# BaseBoard.net
KiCad netlist of a schematic drawn in EAGLE
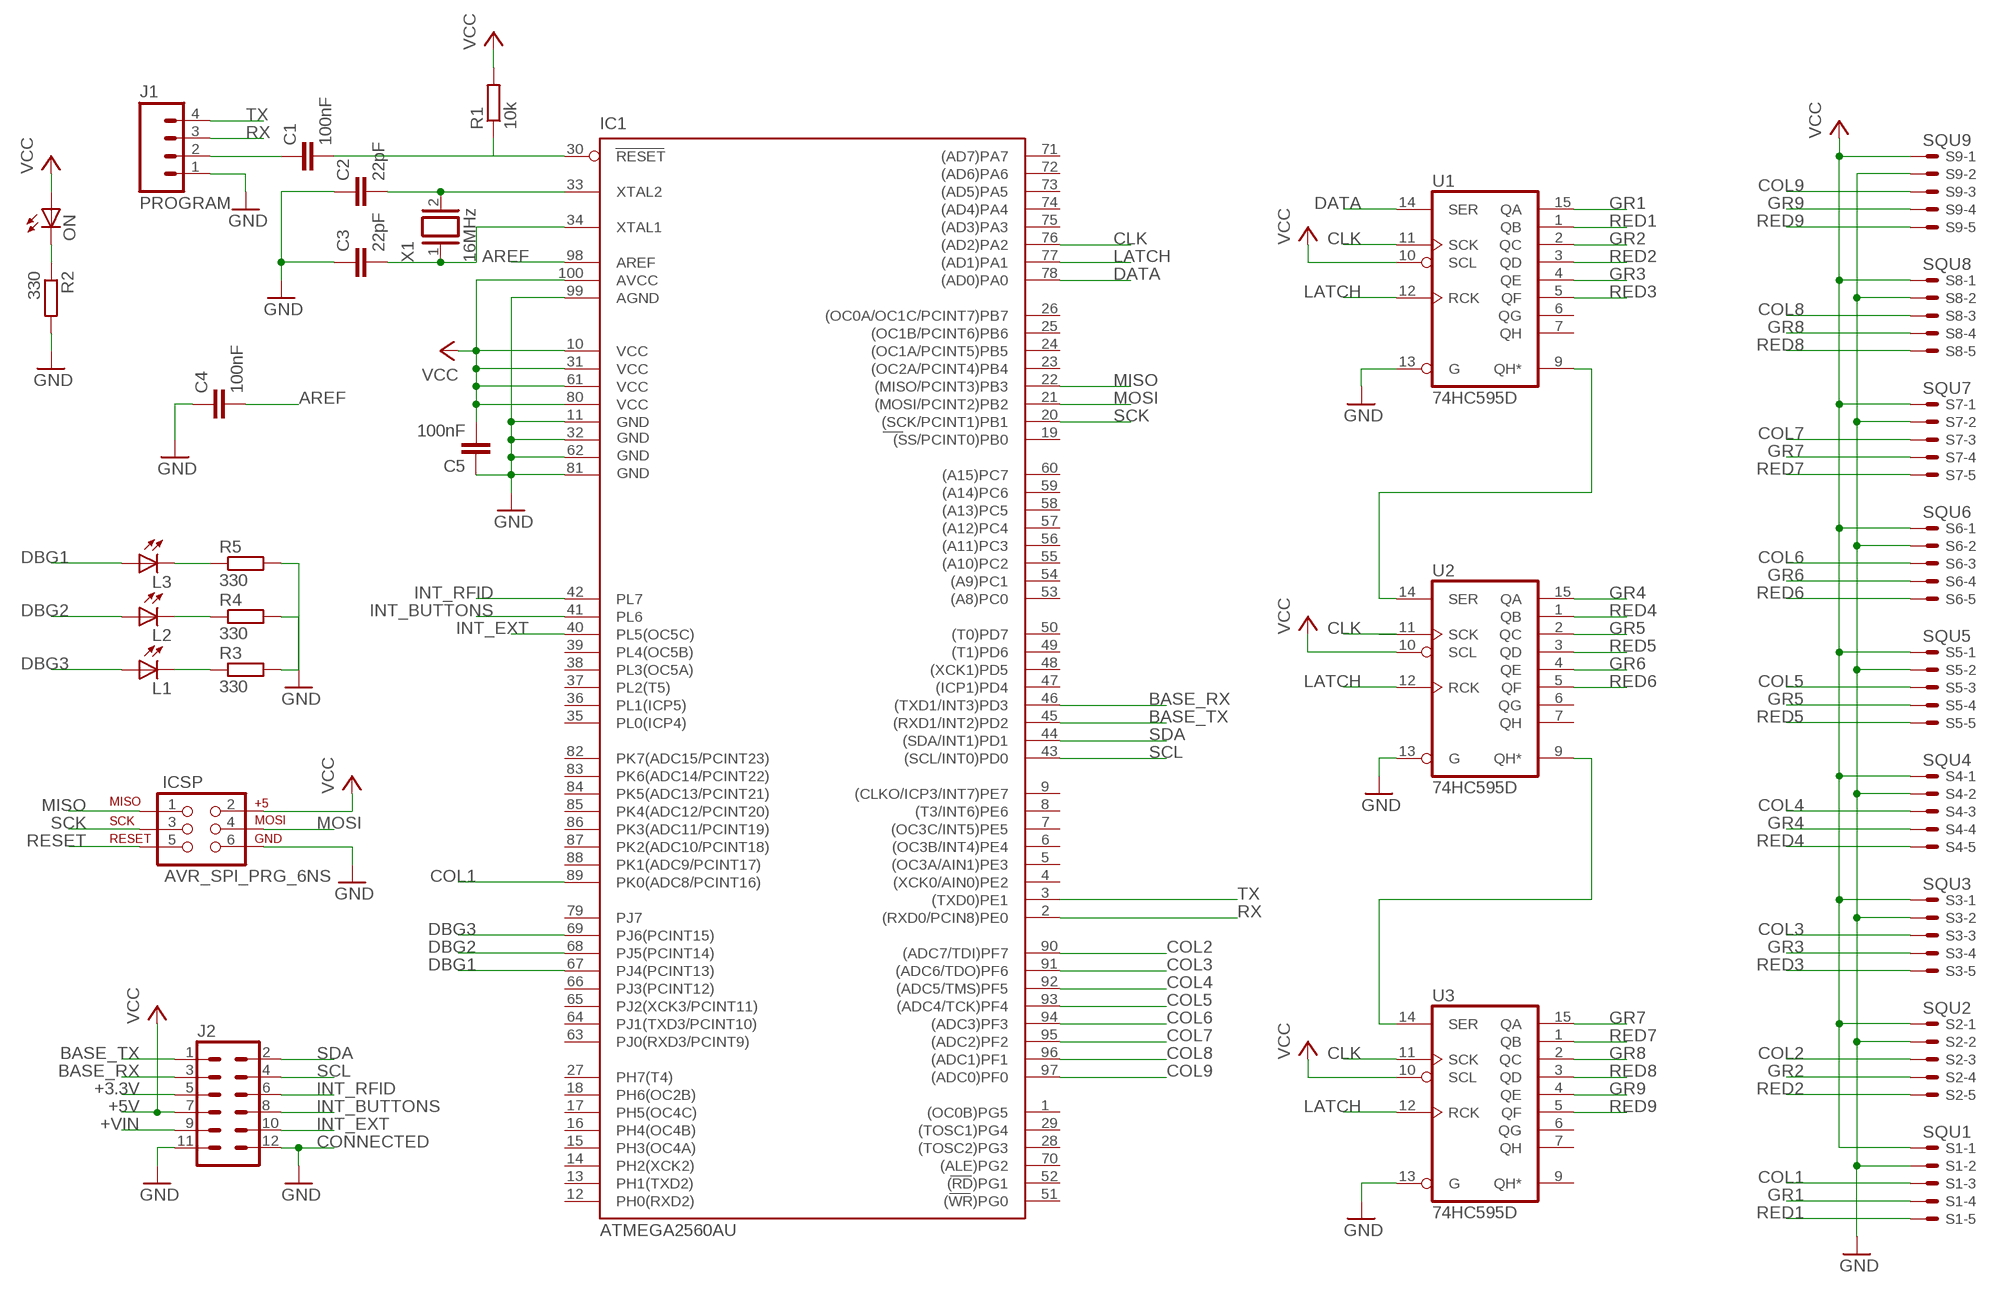
[diagram p0: schematic, sheet 1]

(export (version "E")
  (design (tool "Eeschema 10.0.6"))
  (components
    (comp (ref "C1")
      (value "100nF")
      (footprint "eagle-import:C0805")
      (libsource (lib "eagle-import") (part "C-EUC0805"))
    )
    (comp (ref "C2")
      (value "22pF")
      (footprint "eagle-import:C0805")
      (libsource (lib "eagle-import") (part "C-EUC0805"))
    )
    (comp (ref "C3")
      (value "22pF")
      (footprint "eagle-import:C0805")
      (libsource (lib "eagle-import") (part "C-EUC0805"))
    )
    (comp (ref "C4")
      (value "100nF")
      (footprint "eagle-import:C0805")
      (libsource (lib "eagle-import") (part "C-EUC0805"))
    )
    (comp (ref "C5")
      (value "100nF")
      (footprint "eagle-import:C0805")
      (libsource (lib "eagle-import") (part "C-EUC0805"))
    )
    (comp (ref "IC1")
      (value "ATMEGA2560AU")
      (footprint "eagle-import:TQFP100")
      (libsource (lib "eagle-import") (part "ATMEGA2560AU"))
    )
    (comp (ref "ICSP")
      (value "AVR_SPI_PRG_6NS")
      (footprint "eagle-import:2X3-NS")
      (libsource (lib "eagle-import") (part "AVR_SPI_PRG_6NS"))
    )
    (comp (ref "J1")
      (value "PROGRAM")
      (footprint "eagle-import:1X04")
      (libsource (lib "eagle-import") (part "M04PTH"))
    )
    (comp (ref "J2")
      (value "CON06X2-2MM")
      (footprint "eagle-import:CON06X2_2MM")
      (libsource (lib "eagle-import") (part "CON06X2-2MM"))
    )
    (comp (ref "L1")
      (value "LEDCHIP-LED0805")
      (footprint "eagle-import:CHIP-LED0805")
      (libsource (lib "eagle-import") (part "LEDCHIP-LED0805"))
    )
    (comp (ref "L2")
      (value "LEDCHIP-LED0805")
      (footprint "eagle-import:CHIP-LED0805")
      (libsource (lib "eagle-import") (part "LEDCHIP-LED0805"))
    )
    (comp (ref "L3")
      (value "LEDCHIP-LED0805")
      (footprint "eagle-import:CHIP-LED0805")
      (libsource (lib "eagle-import") (part "LEDCHIP-LED0805"))
    )
    (comp (ref "ON")
      (value "LEDCHIP-LED0805")
      (footprint "eagle-import:CHIP-LED0805")
      (libsource (lib "eagle-import") (part "LEDCHIP-LED0805"))
    )
    (comp (ref "R1")
      (value "10k")
      (footprint "eagle-import:R0805")
      (libsource (lib "eagle-import") (part "R-EU_R0805"))
    )
    (comp (ref "R2")
      (value "330")
      (footprint "eagle-import:R0805")
      (libsource (lib "eagle-import") (part "R-EU_R0805"))
    )
    (comp (ref "R3")
      (value "330")
      (footprint "eagle-import:R0805")
      (libsource (lib "eagle-import") (part "R-EU_R0805"))
    )
    (comp (ref "R4")
      (value "330")
      (footprint "eagle-import:R0805")
      (libsource (lib "eagle-import") (part "R-EU_R0805"))
    )
    (comp (ref "R5")
      (value "330")
      (footprint "eagle-import:R0805")
      (libsource (lib "eagle-import") (part "R-EU_R0805"))
    )
    (comp (ref "S1")
      (value "SQU1")
      (footprint "eagle-import:53261-05")
      (libsource (lib "eagle-import") (part "53?-05261"))
    )
    (comp (ref "S2")
      (value "SQU2")
      (footprint "eagle-import:53261-05")
      (libsource (lib "eagle-import") (part "53?-05261"))
    )
    (comp (ref "S3")
      (value "SQU3")
      (footprint "eagle-import:53261-05")
      (libsource (lib "eagle-import") (part "53?-05261"))
    )
    (comp (ref "S4")
      (value "SQU4")
      (footprint "eagle-import:53261-05")
      (libsource (lib "eagle-import") (part "53?-05261"))
    )
    (comp (ref "S5")
      (value "SQU5")
      (footprint "eagle-import:53261-05")
      (libsource (lib "eagle-import") (part "53?-05261"))
    )
    (comp (ref "S6")
      (value "SQU6")
      (footprint "eagle-import:53261-05")
      (libsource (lib "eagle-import") (part "53?-05261"))
    )
    (comp (ref "S7")
      (value "SQU7")
      (footprint "eagle-import:53261-05")
      (libsource (lib "eagle-import") (part "53?-05261"))
    )
    (comp (ref "S8")
      (value "SQU8")
      (footprint "eagle-import:53261-05")
      (libsource (lib "eagle-import") (part "53?-05261"))
    )
    (comp (ref "S9")
      (value "SQU9")
      (footprint "eagle-import:53261-05")
      (libsource (lib "eagle-import") (part "53?-05261"))
    )
    (comp (ref "U1")
      (value "74HC595D")
      (footprint "eagle-import:SO16")
      (libsource (lib "eagle-import") (part "74595DHC"))
    )
    (comp (ref "U2")
      (value "74HC595D")
      (footprint "eagle-import:SO16")
      (libsource (lib "eagle-import") (part "74595DHC"))
    )
    (comp (ref "U3")
      (value "74HC595D")
      (footprint "eagle-import:SO16")
      (libsource (lib "eagle-import") (part "74595DHC"))
    )
    (comp (ref "X1")
      (value "16MHz")
      (footprint "eagle-import:QS")
      (libsource (lib "eagle-import") (part "XTAL/S"))
    )
  )
  (nets
    (net (code "1") (name "/+3.3V") (class "Default")
      (node (ref "J2") (pin "5") (pinfunction "5_5") (pintype "passive"))
    )
    (net (code "2") (name "/+VIN") (class "Default")
      (node (ref "J2") (pin "9") (pinfunction "9_9") (pintype "passive"))
    )
    (net (code "3") (name "/AREF") (class "Default")
      (node (ref "C4") (pin "2") (pinfunction "2_2") (pintype "passive"))
      (node (ref "IC1") (pin "98") (pinfunction "AREF_98") (pintype "bidirectional"))
    )
    (net (code "4") (name "/BASE_RX") (class "Default")
      (node (ref "IC1") (pin "46") (pinfunction "(TXD1/INT3)PD3_46") (pintype "bidirectional"))
      (node (ref "J2") (pin "3") (pinfunction "3_3") (pintype "passive"))
    )
    (net (code "5") (name "/BASE_TX") (class "Default")
      (node (ref "IC1") (pin "45") (pinfunction "(RXD1/INT2)PD2_45") (pintype "bidirectional"))
      (node (ref "J2") (pin "1") (pinfunction "1_1") (pintype "passive"))
    )
    (net (code "6") (name "/CLK") (class "Default")
      (node (ref "IC1") (pin "76") (pinfunction "(AD2)PA2_76") (pintype "bidirectional"))
      (node (ref "U1") (pin "11") (pinfunction "SCK_11") (pintype "input"))
      (node (ref "U2") (pin "11") (pinfunction "SCK_11") (pintype "input"))
      (node (ref "U3") (pin "11") (pinfunction "SCK_11") (pintype "input"))
    )
    (net (code "7") (name "/COL1") (class "Default")
      (node (ref "IC1") (pin "89") (pinfunction "PK0(ADC8/PCINT16)_89") (pintype "bidirectional"))
      (node (ref "S1") (pin "3") (pinfunction "S_3") (pintype "passive"))
    )
    (net (code "8") (name "/COL2") (class "Default")
      (node (ref "IC1") (pin "90") (pinfunction "(ADC7/TDI)PF7_90") (pintype "bidirectional"))
      (node (ref "S2") (pin "3") (pinfunction "S_3") (pintype "passive"))
    )
    (net (code "9") (name "/COL3") (class "Default")
      (node (ref "IC1") (pin "91") (pinfunction "(ADC6/TDO)PF6_91") (pintype "bidirectional"))
      (node (ref "S3") (pin "3") (pinfunction "S_3") (pintype "passive"))
    )
    (net (code "10") (name "/COL4") (class "Default")
      (node (ref "IC1") (pin "92") (pinfunction "(ADC5/TMS)PF5_92") (pintype "bidirectional"))
      (node (ref "S4") (pin "3") (pinfunction "S_3") (pintype "passive"))
    )
    (net (code "11") (name "/COL5") (class "Default")
      (node (ref "IC1") (pin "93") (pinfunction "(ADC4/TCK)PF4_93") (pintype "bidirectional"))
      (node (ref "S5") (pin "3") (pinfunction "S_3") (pintype "passive"))
    )
    (net (code "12") (name "/COL6") (class "Default")
      (node (ref "IC1") (pin "94") (pinfunction "(ADC3)PF3_94") (pintype "bidirectional"))
      (node (ref "S6") (pin "3") (pinfunction "S_3") (pintype "passive"))
    )
    (net (code "13") (name "/COL7") (class "Default")
      (node (ref "IC1") (pin "95") (pinfunction "(ADC2)PF2_95") (pintype "bidirectional"))
      (node (ref "S7") (pin "3") (pinfunction "S_3") (pintype "passive"))
    )
    (net (code "14") (name "/COL8") (class "Default")
      (node (ref "IC1") (pin "96") (pinfunction "(ADC1)PF1_96") (pintype "bidirectional"))
      (node (ref "S8") (pin "3") (pinfunction "S_3") (pintype "passive"))
    )
    (net (code "15") (name "/COL9") (class "Default")
      (node (ref "IC1") (pin "97") (pinfunction "(ADC0)PF0_97") (pintype "bidirectional"))
      (node (ref "S9") (pin "3") (pinfunction "S_3") (pintype "passive"))
    )
    (net (code "16") (name "/DATA") (class "Default")
      (node (ref "IC1") (pin "78") (pinfunction "(AD0)PA0_78") (pintype "bidirectional"))
      (node (ref "U1") (pin "14") (pinfunction "SER_14") (pintype "input"))
    )
    (net (code "17") (name "/DBG1") (class "Default")
      (node (ref "IC1") (pin "67") (pinfunction "PJ4(PCINT13)_67") (pintype "bidirectional"))
      (node (ref "L3") (pin "A") (pinfunction "A_A") (pintype "passive"))
    )
    (net (code "18") (name "/DBG2") (class "Default")
      (node (ref "IC1") (pin "68") (pinfunction "PJ5(PCINT14)_68") (pintype "bidirectional"))
      (node (ref "L2") (pin "A") (pinfunction "A_A") (pintype "passive"))
    )
    (net (code "19") (name "/DBG3") (class "Default")
      (node (ref "IC1") (pin "69") (pinfunction "PJ6(PCINT15)_69") (pintype "bidirectional"))
      (node (ref "L1") (pin "A") (pinfunction "A_A") (pintype "passive"))
    )
    (net (code "20") (name "/GR1") (class "Default")
      (node (ref "S1") (pin "4") (pinfunction "S_4") (pintype "passive"))
      (node (ref "U1") (pin "15") (pinfunction "QA_15") (pintype "tri_state"))
    )
    (net (code "21") (name "/GR2") (class "Default")
      (node (ref "S2") (pin "4") (pinfunction "S_4") (pintype "passive"))
      (node (ref "U1") (pin "2") (pinfunction "QC_2") (pintype "tri_state"))
    )
    (net (code "22") (name "/GR3") (class "Default")
      (node (ref "S3") (pin "4") (pinfunction "S_4") (pintype "passive"))
      (node (ref "U1") (pin "4") (pinfunction "QE_4") (pintype "tri_state"))
    )
    (net (code "23") (name "/GR4") (class "Default")
      (node (ref "S4") (pin "4") (pinfunction "S_4") (pintype "passive"))
      (node (ref "U2") (pin "15") (pinfunction "QA_15") (pintype "tri_state"))
    )
    (net (code "24") (name "/GR5") (class "Default")
      (node (ref "S5") (pin "4") (pinfunction "S_4") (pintype "passive"))
      (node (ref "U2") (pin "2") (pinfunction "QC_2") (pintype "tri_state"))
    )
    (net (code "25") (name "/GR6") (class "Default")
      (node (ref "S6") (pin "4") (pinfunction "S_4") (pintype "passive"))
      (node (ref "U2") (pin "4") (pinfunction "QE_4") (pintype "tri_state"))
    )
    (net (code "26") (name "/GR7") (class "Default")
      (node (ref "S7") (pin "4") (pinfunction "S_4") (pintype "passive"))
      (node (ref "U3") (pin "15") (pinfunction "QA_15") (pintype "tri_state"))
    )
    (net (code "27") (name "/GR8") (class "Default")
      (node (ref "S8") (pin "4") (pinfunction "S_4") (pintype "passive"))
      (node (ref "U3") (pin "2") (pinfunction "QC_2") (pintype "tri_state"))
    )
    (net (code "28") (name "/GR9") (class "Default")
      (node (ref "S9") (pin "4") (pinfunction "S_4") (pintype "passive"))
      (node (ref "U3") (pin "4") (pinfunction "QE_4") (pintype "tri_state"))
    )
    (net (code "29") (name "/INT_BUTTONS") (class "Default")
      (node (ref "IC1") (pin "41") (pinfunction "PL6_41") (pintype "bidirectional"))
      (node (ref "J2") (pin "8") (pinfunction "8_8") (pintype "passive"))
    )
    (net (code "30") (name "/INT_EXT") (class "Default")
      (node (ref "IC1") (pin "40") (pinfunction "PL5(OC5C)_40") (pintype "bidirectional"))
      (node (ref "J2") (pin "10") (pinfunction "10_10") (pintype "passive"))
    )
    (net (code "31") (name "/INT_RFID") (class "Default")
      (node (ref "IC1") (pin "42") (pinfunction "PL7_42") (pintype "bidirectional"))
      (node (ref "J2") (pin "6") (pinfunction "6_6") (pintype "passive"))
    )
    (net (code "32") (name "/LATCH") (class "Default")
      (node (ref "IC1") (pin "77") (pinfunction "(AD1)PA1_77") (pintype "bidirectional"))
      (node (ref "U1") (pin "12") (pinfunction "RCK_12") (pintype "input"))
      (node (ref "U2") (pin "12") (pinfunction "RCK_12") (pintype "input"))
      (node (ref "U3") (pin "12") (pinfunction "RCK_12") (pintype "input"))
    )
    (net (code "33") (name "/MISO") (class "Default")
      (node (ref "IC1") (pin "22") (pinfunction "(MISO/PCINT3)PB3_22") (pintype "bidirectional"))
      (node (ref "ICSP") (pin "1") (pinfunction "1_1") (pintype "passive"))
    )
    (net (code "34") (name "/MOSI") (class "Default")
      (node (ref "IC1") (pin "21") (pinfunction "(MOSI/PCINT2)PB2_21") (pintype "bidirectional"))
      (node (ref "ICSP") (pin "4") (pinfunction "4_4") (pintype "passive"))
    )
    (net (code "35") (name "/RED1") (class "Default")
      (node (ref "S1") (pin "5") (pinfunction "S_5") (pintype "passive"))
      (node (ref "U1") (pin "1") (pinfunction "QB_1") (pintype "tri_state"))
    )
    (net (code "36") (name "/RED2") (class "Default")
      (node (ref "S2") (pin "5") (pinfunction "S_5") (pintype "passive"))
      (node (ref "U1") (pin "3") (pinfunction "QD_3") (pintype "tri_state"))
    )
    (net (code "37") (name "/RED3") (class "Default")
      (node (ref "S3") (pin "5") (pinfunction "S_5") (pintype "passive"))
      (node (ref "U1") (pin "5") (pinfunction "QF_5") (pintype "tri_state"))
    )
    (net (code "38") (name "/RED4") (class "Default")
      (node (ref "S4") (pin "5") (pinfunction "S_5") (pintype "passive"))
      (node (ref "U2") (pin "1") (pinfunction "QB_1") (pintype "tri_state"))
    )
    (net (code "39") (name "/RED5") (class "Default")
      (node (ref "S5") (pin "5") (pinfunction "S_5") (pintype "passive"))
      (node (ref "U2") (pin "3") (pinfunction "QD_3") (pintype "tri_state"))
    )
    (net (code "40") (name "/RED6") (class "Default")
      (node (ref "S6") (pin "5") (pinfunction "S_5") (pintype "passive"))
      (node (ref "U2") (pin "5") (pinfunction "QF_5") (pintype "tri_state"))
    )
    (net (code "41") (name "/RED7") (class "Default")
      (node (ref "S7") (pin "5") (pinfunction "S_5") (pintype "passive"))
      (node (ref "U3") (pin "1") (pinfunction "QB_1") (pintype "tri_state"))
    )
    (net (code "42") (name "/RED8") (class "Default")
      (node (ref "S8") (pin "5") (pinfunction "S_5") (pintype "passive"))
      (node (ref "U3") (pin "3") (pinfunction "QD_3") (pintype "tri_state"))
    )
    (net (code "43") (name "/RED9") (class "Default")
      (node (ref "S9") (pin "5") (pinfunction "S_5") (pintype "passive"))
      (node (ref "U3") (pin "5") (pinfunction "QF_5") (pintype "tri_state"))
    )
    (net (code "44") (name "/RESET") (class "Default")
      (node (ref "C1") (pin "2") (pinfunction "2_2") (pintype "passive"))
      (node (ref "IC1") (pin "30") (pinfunction "RESET_30") (pintype "input"))
      (node (ref "ICSP") (pin "5") (pinfunction "5_5") (pintype "passive"))
      (node (ref "R1") (pin "1") (pinfunction "1_1") (pintype "passive"))
    )
    (net (code "45") (name "/RX") (class "Default")
      (node (ref "IC1") (pin "2") (pinfunction "(RXD0/PCIN8)PE0_2") (pintype "bidirectional"))
      (node (ref "J1") (pin "3") (pinfunction "3_3") (pintype "passive"))
    )
    (net (code "46") (name "/SCK") (class "Default")
      (node (ref "IC1") (pin "20") (pinfunction "(SCK/PCINT1)PB1_20") (pintype "bidirectional"))
      (node (ref "ICSP") (pin "3") (pinfunction "3_3") (pintype "passive"))
    )
    (net (code "47") (name "/SCL") (class "Default")
      (node (ref "IC1") (pin "43") (pinfunction "(SCL/INT0)PD0_43") (pintype "bidirectional"))
      (node (ref "J2") (pin "4") (pinfunction "4_4") (pintype "passive"))
    )
    (net (code "48") (name "/SDA") (class "Default")
      (node (ref "IC1") (pin "44") (pinfunction "(SDA/INT1)PD1_44") (pintype "bidirectional"))
      (node (ref "J2") (pin "2") (pinfunction "2_2") (pintype "passive"))
    )
    (net (code "49") (name "/TX") (class "Default")
      (node (ref "IC1") (pin "3") (pinfunction "(TXD0)PE1_3") (pintype "bidirectional"))
      (node (ref "J1") (pin "4") (pinfunction "4_4") (pintype "passive"))
    )
    (net (code "50") (name "GND") (class "Default")
      (node (ref "C2") (pin "1") (pinfunction "1_1") (pintype "passive"))
      (node (ref "C3") (pin "1") (pinfunction "1_1") (pintype "passive"))
      (node (ref "C4") (pin "1") (pinfunction "1_1") (pintype "passive"))
      (node (ref "C5") (pin "1") (pinfunction "1_1") (pintype "passive"))
      (node (ref "IC1") (pin "11") (pinfunction "GND_11") (pintype "power_in"))
      (node (ref "IC1") (pin "32") (pinfunction "GND1_32") (pintype "power_in"))
      (node (ref "IC1") (pin "62") (pinfunction "GND2_62") (pintype "power_in"))
      (node (ref "IC1") (pin "81") (pinfunction "GND3_81") (pintype "power_in"))
      (node (ref "IC1") (pin "99") (pinfunction "AGND_99") (pintype "power_in"))
      (node (ref "ICSP") (pin "6") (pinfunction "6_6") (pintype "passive"))
      (node (ref "J1") (pin "1") (pinfunction "1_1") (pintype "passive"))
      (node (ref "J2") (pin "11") (pinfunction "11_11") (pintype "passive"))
      (node (ref "J2") (pin "12") (pinfunction "12_12") (pintype "passive"))
      (node (ref "R2") (pin "2") (pinfunction "2_2") (pintype "passive"))
      (node (ref "R3") (pin "2") (pinfunction "2_2") (pintype "passive"))
      (node (ref "R4") (pin "2") (pinfunction "2_2") (pintype "passive"))
      (node (ref "R5") (pin "2") (pinfunction "2_2") (pintype "passive"))
      (node (ref "S1") (pin "2") (pinfunction "S_2") (pintype "passive"))
      (node (ref "S2") (pin "2") (pinfunction "S_2") (pintype "passive"))
      (node (ref "S3") (pin "2") (pinfunction "S_2") (pintype "passive"))
      (node (ref "S4") (pin "2") (pinfunction "S_2") (pintype "passive"))
      (node (ref "S5") (pin "2") (pinfunction "S_2") (pintype "passive"))
      (node (ref "S6") (pin "2") (pinfunction "S_2") (pintype "passive"))
      (node (ref "S7") (pin "2") (pinfunction "S_2") (pintype "passive"))
      (node (ref "S8") (pin "2") (pinfunction "S_2") (pintype "passive"))
      (node (ref "S9") (pin "2") (pinfunction "S_2") (pintype "passive"))
      (node (ref "U1") (pin "13") (pinfunction "G_13") (pintype "input"))
      (node (ref "U2") (pin "13") (pinfunction "G_13") (pintype "input"))
      (node (ref "U3") (pin "13") (pinfunction "G_13") (pintype "input"))
    )
    (net (code "51") (name "Net-(C1-Pad1)") (class "Default")
      (node (ref "C1") (pin "1") (pinfunction "1_1") (pintype "passive"))
      (node (ref "J1") (pin "2") (pinfunction "2_2") (pintype "passive"))
    )
    (net (code "52") (name "Net-(IC1-XTAL1)") (class "Default")
      (node (ref "C3") (pin "2") (pinfunction "2_2") (pintype "passive"))
      (node (ref "IC1") (pin "34") (pinfunction "XTAL1_34") (pintype "input"))
      (node (ref "X1") (pin "1") (pinfunction "1_1") (pintype "passive"))
    )
    (net (code "53") (name "Net-(IC1-XTAL2)") (class "Default")
      (node (ref "C2") (pin "2") (pinfunction "2_2") (pintype "passive"))
      (node (ref "IC1") (pin "33") (pinfunction "XTAL2_33") (pintype "output"))
      (node (ref "X1") (pin "2") (pinfunction "2_2") (pintype "passive"))
    )
    (net (code "54") (name "Net-(L1-PadC)") (class "Default")
      (node (ref "L1") (pin "C") (pinfunction "C_C") (pintype "passive"))
      (node (ref "R3") (pin "1") (pinfunction "1_1") (pintype "passive"))
    )
    (net (code "55") (name "Net-(L2-PadC)") (class "Default")
      (node (ref "L2") (pin "C") (pinfunction "C_C") (pintype "passive"))
      (node (ref "R4") (pin "1") (pinfunction "1_1") (pintype "passive"))
    )
    (net (code "56") (name "Net-(L3-PadC)") (class "Default")
      (node (ref "L3") (pin "C") (pinfunction "C_C") (pintype "passive"))
      (node (ref "R5") (pin "1") (pinfunction "1_1") (pintype "passive"))
    )
    (net (code "57") (name "Net-(ON-PadC)") (class "Default")
      (node (ref "ON") (pin "C") (pinfunction "C_C") (pintype "passive"))
      (node (ref "R2") (pin "1") (pinfunction "1_1") (pintype "passive"))
    )
    (net (code "58") (name "Net-(U1A-QH*)") (class "Default")
      (node (ref "U1") (pin "9") (pinfunction "QH*_9") (pintype "tri_state"))
      (node (ref "U2") (pin "14") (pinfunction "SER_14") (pintype "input"))
    )
    (net (code "59") (name "Net-(U2A-QH*)") (class "Default")
      (node (ref "U2") (pin "9") (pinfunction "QH*_9") (pintype "tri_state"))
      (node (ref "U3") (pin "14") (pinfunction "SER_14") (pintype "input"))
    )
    (net (code "60") (name "VCC") (class "Default")
      (node (ref "C5") (pin "2") (pinfunction "2_2") (pintype "passive"))
      (node (ref "IC1") (pin "10") (pinfunction "VCC_10") (pintype "power_in"))
      (node (ref "IC1") (pin "100") (pinfunction "AVCC_100") (pintype "power_in"))
      (node (ref "IC1") (pin "31") (pinfunction "VCC1_31") (pintype "power_in"))
      (node (ref "IC1") (pin "61") (pinfunction "VCC2_61") (pintype "power_in"))
      (node (ref "IC1") (pin "80") (pinfunction "VCC3_80") (pintype "power_in"))
      (node (ref "ICSP") (pin "2") (pinfunction "2_2") (pintype "passive"))
      (node (ref "J2") (pin "7") (pinfunction "7_7") (pintype "passive"))
      (node (ref "ON") (pin "A") (pinfunction "A_A") (pintype "passive"))
      (node (ref "R1") (pin "2") (pinfunction "2_2") (pintype "passive"))
      (node (ref "S1") (pin "1") (pinfunction "S_1") (pintype "passive"))
      (node (ref "S2") (pin "1") (pinfunction "S_1") (pintype "passive"))
      (node (ref "S3") (pin "1") (pinfunction "S_1") (pintype "passive"))
      (node (ref "S4") (pin "1") (pinfunction "S_1") (pintype "passive"))
      (node (ref "S5") (pin "1") (pinfunction "S_1") (pintype "passive"))
      (node (ref "S6") (pin "1") (pinfunction "S_1") (pintype "passive"))
      (node (ref "S7") (pin "1") (pinfunction "S_1") (pintype "passive"))
      (node (ref "S8") (pin "1") (pinfunction "S_1") (pintype "passive"))
      (node (ref "S9") (pin "1") (pinfunction "S_1") (pintype "passive"))
      (node (ref "U1") (pin "10") (pinfunction "SCL_10") (pintype "input"))
      (node (ref "U2") (pin "10") (pinfunction "SCL_10") (pintype "input"))
      (node (ref "U3") (pin "10") (pinfunction "SCL_10") (pintype "input"))
    )
    (net (code "61") (name "unconnected-(IC1-(A8)PC0-Pad53)") (class "Default")
      (node (ref "IC1") (pin "53") (pinfunction "(A8)PC0_53") (pintype "bidirectional"))
    )
    (net (code "62") (name "unconnected-(IC1-(A9)PC1-Pad54)") (class "Default")
      (node (ref "IC1") (pin "54") (pinfunction "(A9)PC1_54") (pintype "bidirectional"))
    )
    (net (code "63") (name "unconnected-(IC1-(A10)PC2-Pad55)") (class "Default")
      (node (ref "IC1") (pin "55") (pinfunction "(A10)PC2_55") (pintype "bidirectional"))
    )
    (net (code "64") (name "unconnected-(IC1-(A11)PC3-Pad56)") (class "Default")
      (node (ref "IC1") (pin "56") (pinfunction "(A11)PC3_56") (pintype "bidirectional"))
    )
    (net (code "65") (name "unconnected-(IC1-(A12)PC4-Pad57)") (class "Default")
      (node (ref "IC1") (pin "57") (pinfunction "(A12)PC4_57") (pintype "bidirectional"))
    )
    (net (code "66") (name "unconnected-(IC1-(A13)PC5-Pad58)") (class "Default")
      (node (ref "IC1") (pin "58") (pinfunction "(A13)PC5_58") (pintype "bidirectional"))
    )
    (net (code "67") (name "unconnected-(IC1-(A14)PC6-Pad59)") (class "Default")
      (node (ref "IC1") (pin "59") (pinfunction "(A14)PC6_59") (pintype "bidirectional"))
    )
    (net (code "68") (name "unconnected-(IC1-(A15)PC7-Pad60)") (class "Default")
      (node (ref "IC1") (pin "60") (pinfunction "(A15)PC7_60") (pintype "bidirectional"))
    )
    (net (code "69") (name "unconnected-(IC1-(AD3)PA3-Pad75)") (class "Default")
      (node (ref "IC1") (pin "75") (pinfunction "(AD3)PA3_75") (pintype "bidirectional"))
    )
    (net (code "70") (name "unconnected-(IC1-(AD4)PA4-Pad74)") (class "Default")
      (node (ref "IC1") (pin "74") (pinfunction "(AD4)PA4_74") (pintype "bidirectional"))
    )
    (net (code "71") (name "unconnected-(IC1-(AD5)PA5-Pad73)") (class "Default")
      (node (ref "IC1") (pin "73") (pinfunction "(AD5)PA5_73") (pintype "bidirectional"))
    )
    (net (code "72") (name "unconnected-(IC1-(AD6)PA6-Pad72)") (class "Default")
      (node (ref "IC1") (pin "72") (pinfunction "(AD6)PA6_72") (pintype "bidirectional"))
    )
    (net (code "73") (name "unconnected-(IC1-(AD7)PA7-Pad71)") (class "Default")
      (node (ref "IC1") (pin "71") (pinfunction "(AD7)PA7_71") (pintype "bidirectional"))
    )
    (net (code "74") (name "unconnected-(IC1-(ALE)PG2-Pad70)") (class "Default")
      (node (ref "IC1") (pin "70") (pinfunction "(ALE)PG2_70") (pintype "bidirectional"))
    )
    (net (code "75") (name "unconnected-(IC1-(CLKO{slash}ICP3{slash}INT7)PE7-Pad9)") (class "Default")
      (node (ref "IC1") (pin "9") (pinfunction "(CLKO/ICP3/INT7)PE7_9") (pintype "bidirectional"))
    )
    (net (code "76") (name "unconnected-(IC1-(ICP1)PD4-Pad47)") (class "Default")
      (node (ref "IC1") (pin "47") (pinfunction "(ICP1)PD4_47") (pintype "bidirectional"))
    )
    (net (code "77") (name "unconnected-(IC1-(OC0A{slash}OC1C{slash}PCINT7)PB7-Pad26)") (class "Default")
      (node (ref "IC1") (pin "26") (pinfunction "(OC0A/OC1C/PCINT7)PB7_26") (pintype "bidirectional"))
    )
    (net (code "78") (name "unconnected-(IC1-(OC0B)PG5-Pad1)") (class "Default")
      (node (ref "IC1") (pin "1") (pinfunction "(OC0B)PG5_1") (pintype "bidirectional"))
    )
    (net (code "79") (name "unconnected-(IC1-(OC1A{slash}PCINT5)PB5-Pad24)") (class "Default")
      (node (ref "IC1") (pin "24") (pinfunction "(OC1A/PCINT5)PB5_24") (pintype "bidirectional"))
    )
    (net (code "80") (name "unconnected-(IC1-(OC1B{slash}PCINT6)PB6-Pad25)") (class "Default")
      (node (ref "IC1") (pin "25") (pinfunction "(OC1B/PCINT6)PB6_25") (pintype "bidirectional"))
    )
    (net (code "81") (name "unconnected-(IC1-(OC2A{slash}PCINT4)PB4-Pad23)") (class "Default")
      (node (ref "IC1") (pin "23") (pinfunction "(OC2A/PCINT4)PB4_23") (pintype "bidirectional"))
    )
    (net (code "82") (name "unconnected-(IC1-(OC3A{slash}AIN1)PE3-Pad5)") (class "Default")
      (node (ref "IC1") (pin "5") (pinfunction "(OC3A/AIN1)PE3_5") (pintype "bidirectional"))
    )
    (net (code "83") (name "unconnected-(IC1-(OC3B{slash}INT4)PE4-Pad6)") (class "Default")
      (node (ref "IC1") (pin "6") (pinfunction "(OC3B/INT4)PE4_6") (pintype "bidirectional"))
    )
    (net (code "84") (name "unconnected-(IC1-(OC3C{slash}INT5)PE5-Pad7)") (class "Default")
      (node (ref "IC1") (pin "7") (pinfunction "(OC3C/INT5)PE5_7") (pintype "bidirectional"))
    )
    (net (code "85") (name "unconnected-(IC1-(RD)PG1-Pad52)") (class "Default")
      (node (ref "IC1") (pin "52") (pinfunction "(RD)PG1_52") (pintype "bidirectional"))
    )
    (net (code "86") (name "unconnected-(IC1-(SS{slash}PCINT0)PB0-Pad19)") (class "Default")
      (node (ref "IC1") (pin "19") (pinfunction "(SS/PCINT0)PB0_19") (pintype "bidirectional"))
    )
    (net (code "87") (name "unconnected-(IC1-(T0)PD7-Pad50)") (class "Default")
      (node (ref "IC1") (pin "50") (pinfunction "(T0)PD7_50") (pintype "bidirectional"))
    )
    (net (code "88") (name "unconnected-(IC1-(T1)PD6-Pad49)") (class "Default")
      (node (ref "IC1") (pin "49") (pinfunction "(T1)PD6_49") (pintype "bidirectional"))
    )
    (net (code "89") (name "unconnected-(IC1-(T3{slash}INT6)PE6-Pad8)") (class "Default")
      (node (ref "IC1") (pin "8") (pinfunction "(T3/INT6)PE6_8") (pintype "bidirectional"))
    )
    (net (code "90") (name "unconnected-(IC1-(TOSC1)PG4-Pad29)") (class "Default")
      (node (ref "IC1") (pin "29") (pinfunction "(TOSC1)PG4_29") (pintype "bidirectional"))
    )
    (net (code "91") (name "unconnected-(IC1-(TOSC2)PG3-Pad28)") (class "Default")
      (node (ref "IC1") (pin "28") (pinfunction "(TOSC2)PG3_28") (pintype "bidirectional"))
    )
    (net (code "92") (name "unconnected-(IC1-(WR)PG0-Pad51)") (class "Default")
      (node (ref "IC1") (pin "51") (pinfunction "(WR)PG0_51") (pintype "bidirectional"))
    )
    (net (code "93") (name "unconnected-(IC1-(XCK0{slash}AIN0)PE2-Pad4)") (class "Default")
      (node (ref "IC1") (pin "4") (pinfunction "(XCK0/AIN0)PE2_4") (pintype "bidirectional"))
    )
    (net (code "94") (name "unconnected-(IC1-(XCK1)PD5-Pad48)") (class "Default")
      (node (ref "IC1") (pin "48") (pinfunction "(XCK1)PD5_48") (pintype "bidirectional"))
    )
    (net (code "95") (name "unconnected-(IC1-PH0(RXD2)-Pad12)") (class "Default")
      (node (ref "IC1") (pin "12") (pinfunction "PH0(RXD2)_12") (pintype "bidirectional"))
    )
    (net (code "96") (name "unconnected-(IC1-PH1(TXD2)-Pad13)") (class "Default")
      (node (ref "IC1") (pin "13") (pinfunction "PH1(TXD2)_13") (pintype "bidirectional"))
    )
    (net (code "97") (name "unconnected-(IC1-PH2(XCK2)-Pad14)") (class "Default")
      (node (ref "IC1") (pin "14") (pinfunction "PH2(XCK2)_14") (pintype "bidirectional"))
    )
    (net (code "98") (name "unconnected-(IC1-PH3(OC4A)-Pad15)") (class "Default")
      (node (ref "IC1") (pin "15") (pinfunction "PH3(OC4A)_15") (pintype "bidirectional"))
    )
    (net (code "99") (name "unconnected-(IC1-PH4(OC4B)-Pad16)") (class "Default")
      (node (ref "IC1") (pin "16") (pinfunction "PH4(OC4B)_16") (pintype "bidirectional"))
    )
    (net (code "100") (name "unconnected-(IC1-PH5(OC4C)-Pad17)") (class "Default")
      (node (ref "IC1") (pin "17") (pinfunction "PH5(OC4C)_17") (pintype "bidirectional"))
    )
    (net (code "101") (name "unconnected-(IC1-PH6(OC2B)-Pad18)") (class "Default")
      (node (ref "IC1") (pin "18") (pinfunction "PH6(OC2B)_18") (pintype "bidirectional"))
    )
    (net (code "102") (name "unconnected-(IC1-PH7(T4)-Pad27)") (class "Default")
      (node (ref "IC1") (pin "27") (pinfunction "PH7(T4)_27") (pintype "bidirectional"))
    )
    (net (code "103") (name "unconnected-(IC1-PJ0(RXD3{slash}PCINT9)-Pad63)") (class "Default")
      (node (ref "IC1") (pin "63") (pinfunction "PJ0(RXD3/PCINT9)_63") (pintype "bidirectional"))
    )
    (net (code "104") (name "unconnected-(IC1-PJ1(TXD3{slash}PCINT10)-Pad64)") (class "Default")
      (node (ref "IC1") (pin "64") (pinfunction "PJ1(TXD3/PCINT10)_64") (pintype "bidirectional"))
    )
    (net (code "105") (name "unconnected-(IC1-PJ2(XCK3{slash}PCINT11)-Pad65)") (class "Default")
      (node (ref "IC1") (pin "65") (pinfunction "PJ2(XCK3/PCINT11)_65") (pintype "bidirectional"))
    )
    (net (code "106") (name "unconnected-(IC1-PJ3(PCINT12)-Pad66)") (class "Default")
      (node (ref "IC1") (pin "66") (pinfunction "PJ3(PCINT12)_66") (pintype "bidirectional"))
    )
    (net (code "107") (name "unconnected-(IC1-PJ7-Pad79)") (class "Default")
      (node (ref "IC1") (pin "79") (pinfunction "PJ7_79") (pintype "bidirectional"))
    )
    (net (code "108") (name "unconnected-(IC1-PK1(ADC9{slash}PCINT17)-Pad88)") (class "Default")
      (node (ref "IC1") (pin "88") (pinfunction "PK1(ADC9/PCINT17)_88") (pintype "bidirectional"))
    )
    (net (code "109") (name "unconnected-(IC1-PK2(ADC10{slash}PCINT18)-Pad87)") (class "Default")
      (node (ref "IC1") (pin "87") (pinfunction "PK2(ADC10/PCINT18)_87") (pintype "bidirectional"))
    )
    (net (code "110") (name "unconnected-(IC1-PK3(ADC11{slash}PCINT19)-Pad86)") (class "Default")
      (node (ref "IC1") (pin "86") (pinfunction "PK3(ADC11/PCINT19)_86") (pintype "bidirectional"))
    )
    (net (code "111") (name "unconnected-(IC1-PK4(ADC12{slash}PCINT20)-Pad85)") (class "Default")
      (node (ref "IC1") (pin "85") (pinfunction "PK4(ADC12/PCINT20)_85") (pintype "bidirectional"))
    )
    (net (code "112") (name "unconnected-(IC1-PK5(ADC13{slash}PCINT21)-Pad84)") (class "Default")
      (node (ref "IC1") (pin "84") (pinfunction "PK5(ADC13/PCINT21)_84") (pintype "bidirectional"))
    )
    (net (code "113") (name "unconnected-(IC1-PK6(ADC14{slash}PCINT22)-Pad83)") (class "Default")
      (node (ref "IC1") (pin "83") (pinfunction "PK6(ADC14/PCINT22)_83") (pintype "bidirectional"))
    )
    (net (code "114") (name "unconnected-(IC1-PK7(ADC15{slash}PCINT23)-Pad82)") (class "Default")
      (node (ref "IC1") (pin "82") (pinfunction "PK7(ADC15/PCINT23)_82") (pintype "bidirectional"))
    )
    (net (code "115") (name "unconnected-(IC1-PL0(ICP4)-Pad35)") (class "Default")
      (node (ref "IC1") (pin "35") (pinfunction "PL0(ICP4)_35") (pintype "bidirectional"))
    )
    (net (code "116") (name "unconnected-(IC1-PL1(ICP5)-Pad36)") (class "Default")
      (node (ref "IC1") (pin "36") (pinfunction "PL1(ICP5)_36") (pintype "bidirectional"))
    )
    (net (code "117") (name "unconnected-(IC1-PL2(T5)-Pad37)") (class "Default")
      (node (ref "IC1") (pin "37") (pinfunction "PL2(T5)_37") (pintype "bidirectional"))
    )
    (net (code "118") (name "unconnected-(IC1-PL3(OC5A)-Pad38)") (class "Default")
      (node (ref "IC1") (pin "38") (pinfunction "PL3(OC5A)_38") (pintype "bidirectional"))
    )
    (net (code "119") (name "unconnected-(IC1-PL4(OC5B)-Pad39)") (class "Default")
      (node (ref "IC1") (pin "39") (pinfunction "PL4(OC5B)_39") (pintype "bidirectional"))
    )
    (net (code "120") (name "unconnected-(U1A-QG-Pad6)") (class "Default")
      (node (ref "U1") (pin "6") (pinfunction "QG_6") (pintype "tri_state"))
    )
    (net (code "121") (name "unconnected-(U1A-QH-Pad7)") (class "Default")
      (node (ref "U1") (pin "7") (pinfunction "QH_7") (pintype "tri_state"))
    )
    (net (code "122") (name "unconnected-(U2A-QG-Pad6)") (class "Default")
      (node (ref "U2") (pin "6") (pinfunction "QG_6") (pintype "tri_state"))
    )
    (net (code "123") (name "unconnected-(U2A-QH-Pad7)") (class "Default")
      (node (ref "U2") (pin "7") (pinfunction "QH_7") (pintype "tri_state"))
    )
    (net (code "124") (name "unconnected-(U3A-QG-Pad6)") (class "Default")
      (node (ref "U3") (pin "6") (pinfunction "QG_6") (pintype "tri_state"))
    )
    (net (code "125") (name "unconnected-(U3A-QH*-Pad9)") (class "Default")
      (node (ref "U3") (pin "9") (pinfunction "QH*_9") (pintype "tri_state"))
    )
    (net (code "126") (name "unconnected-(U3A-QH-Pad7)") (class "Default")
      (node (ref "U3") (pin "7") (pinfunction "QH_7") (pintype "tri_state"))
    )
  )
)
